# SkyNetV3main.net
KiCad netlist of a schematic drawn in EAGLE
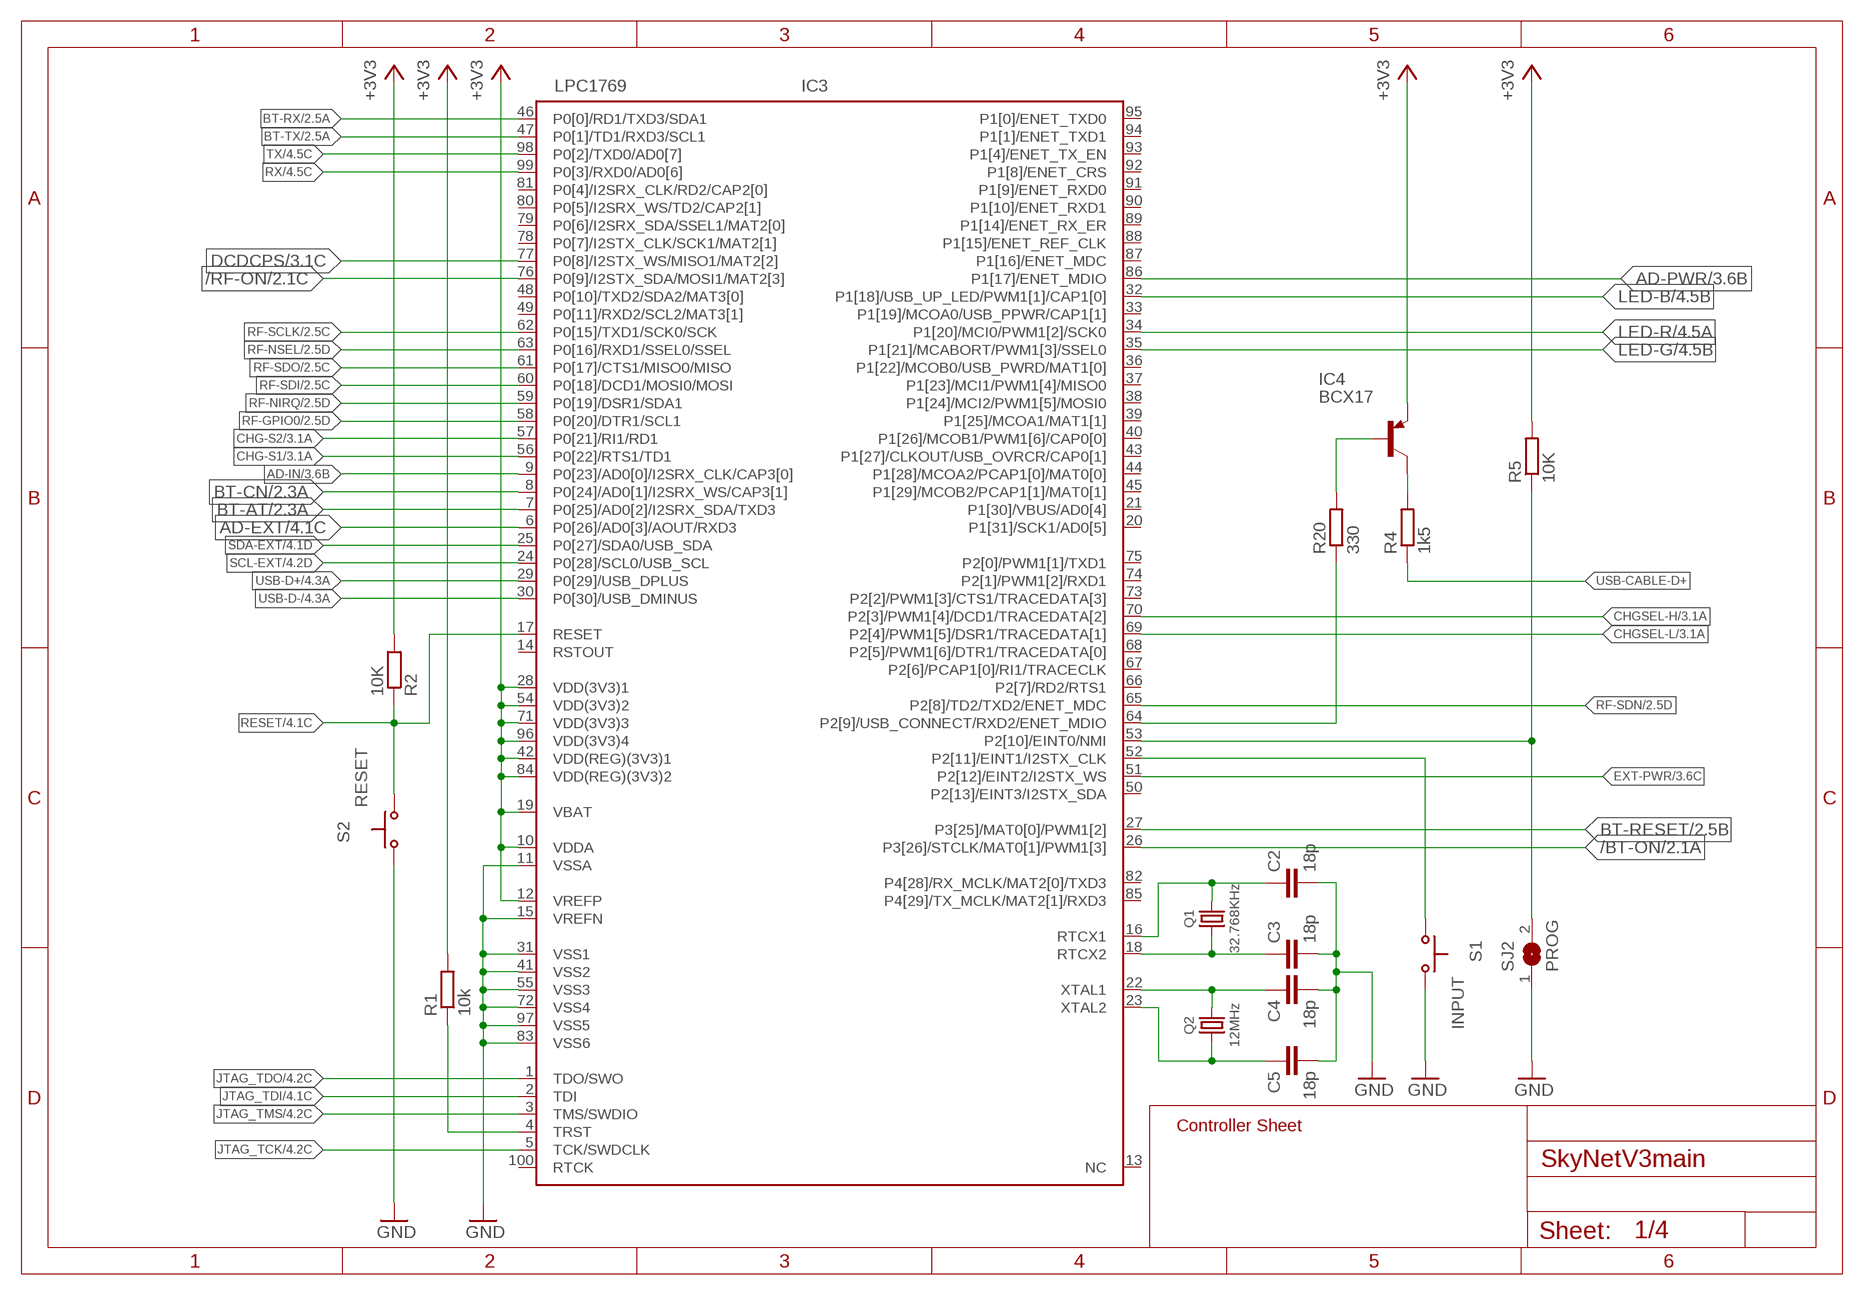
[diagram p0: schematic, sheet 1]
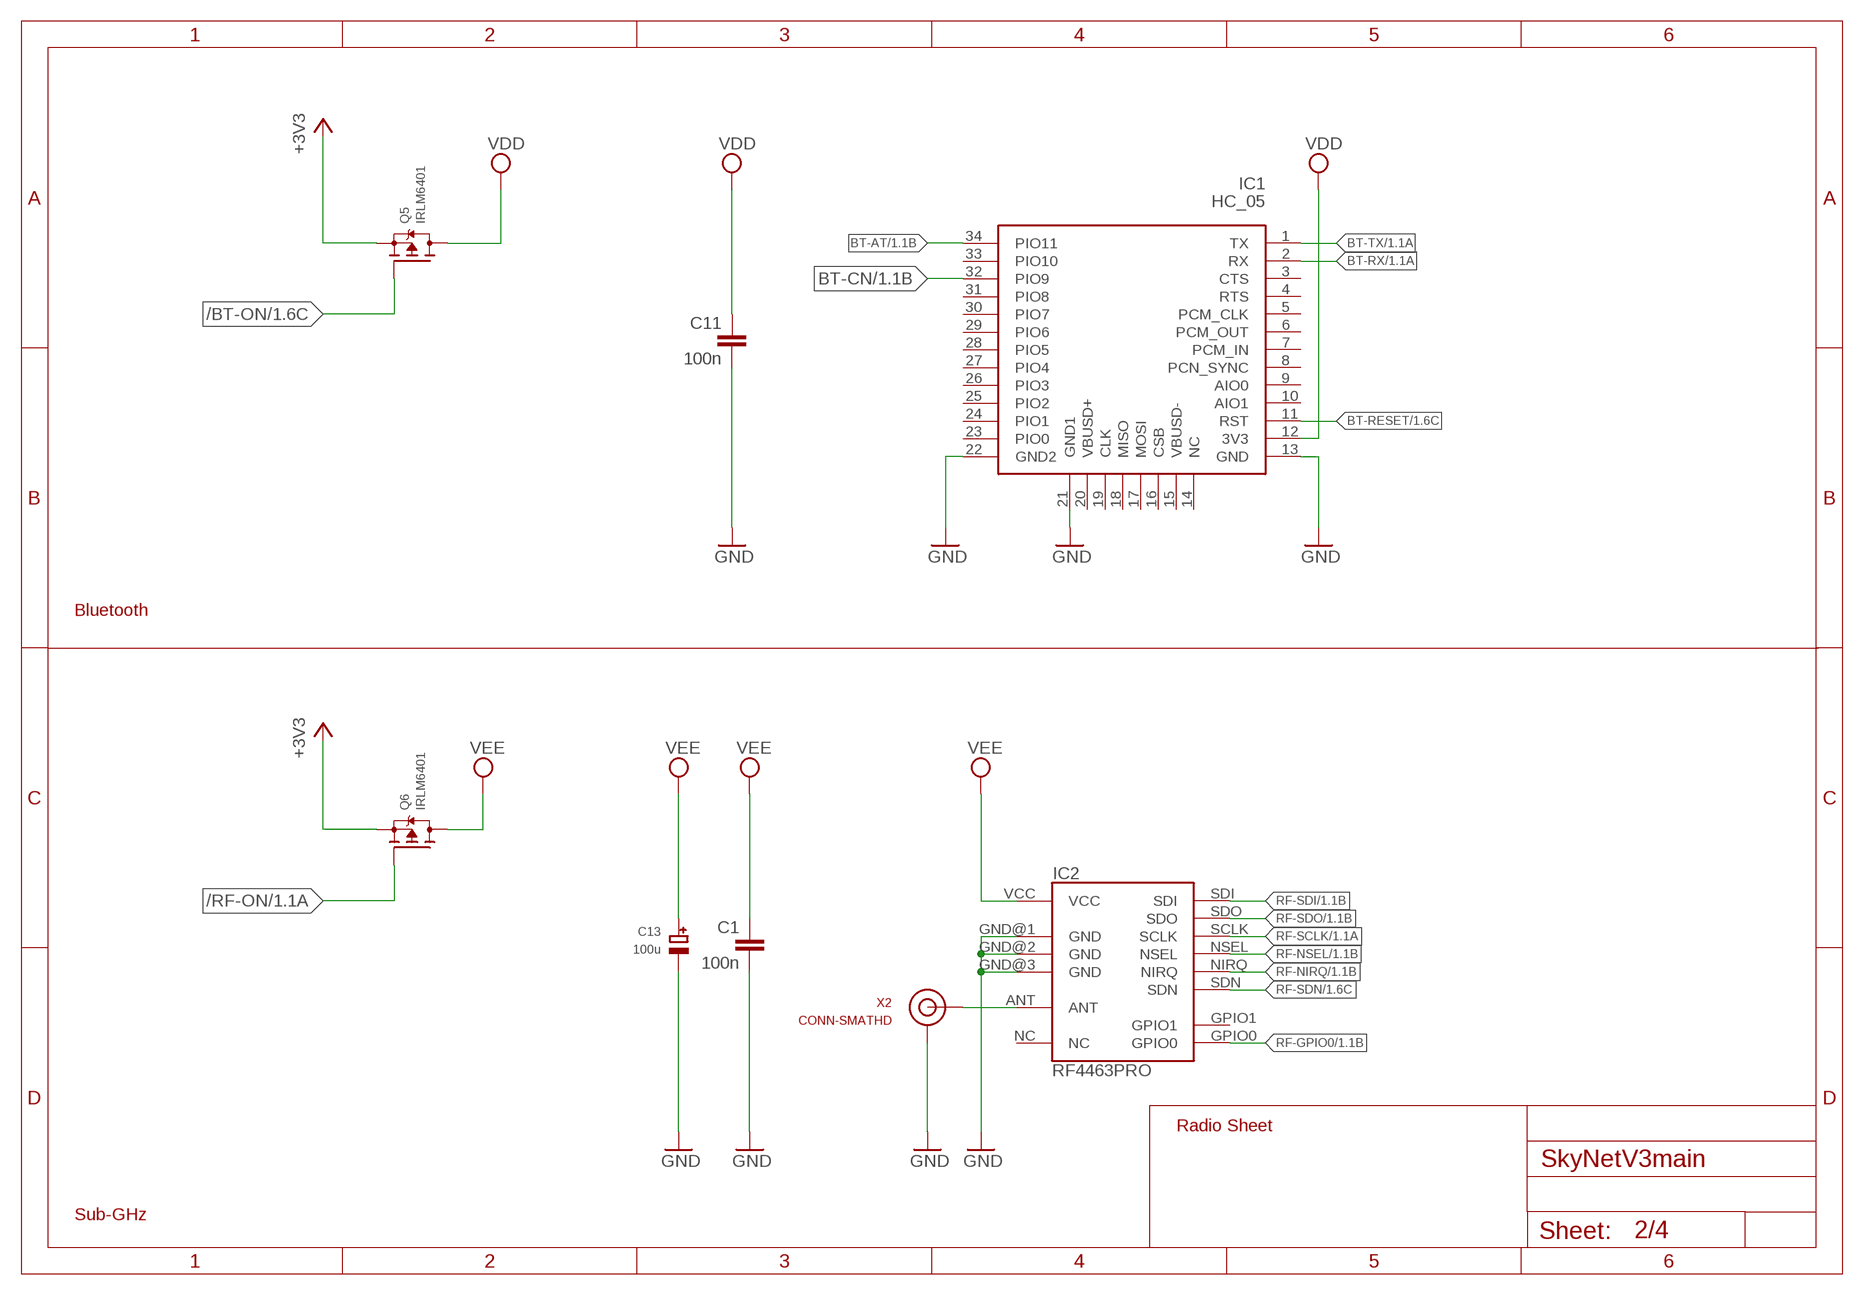
[diagram p1: schematic, sheet 2]
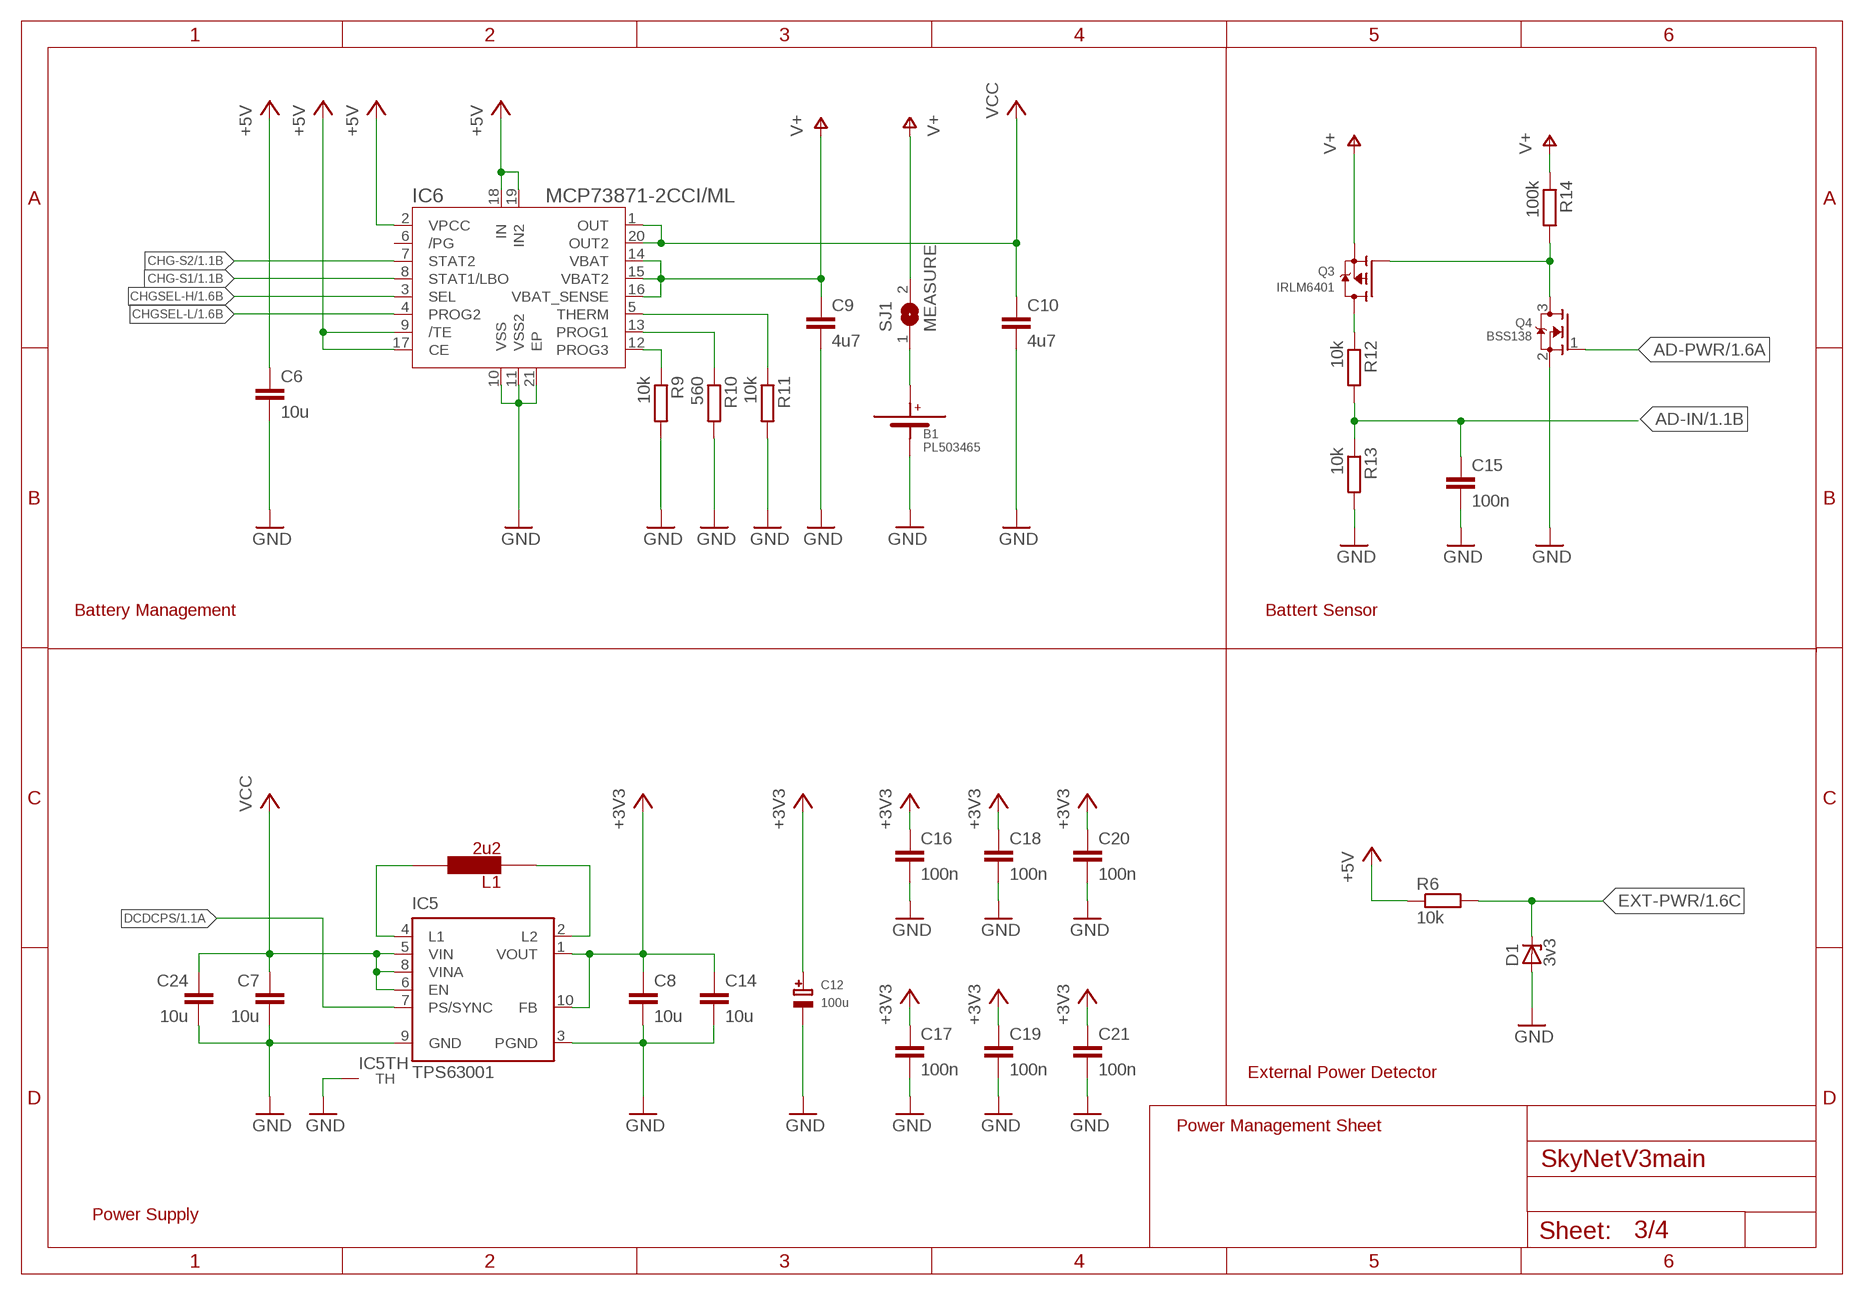
[diagram p2: schematic, sheet 3]
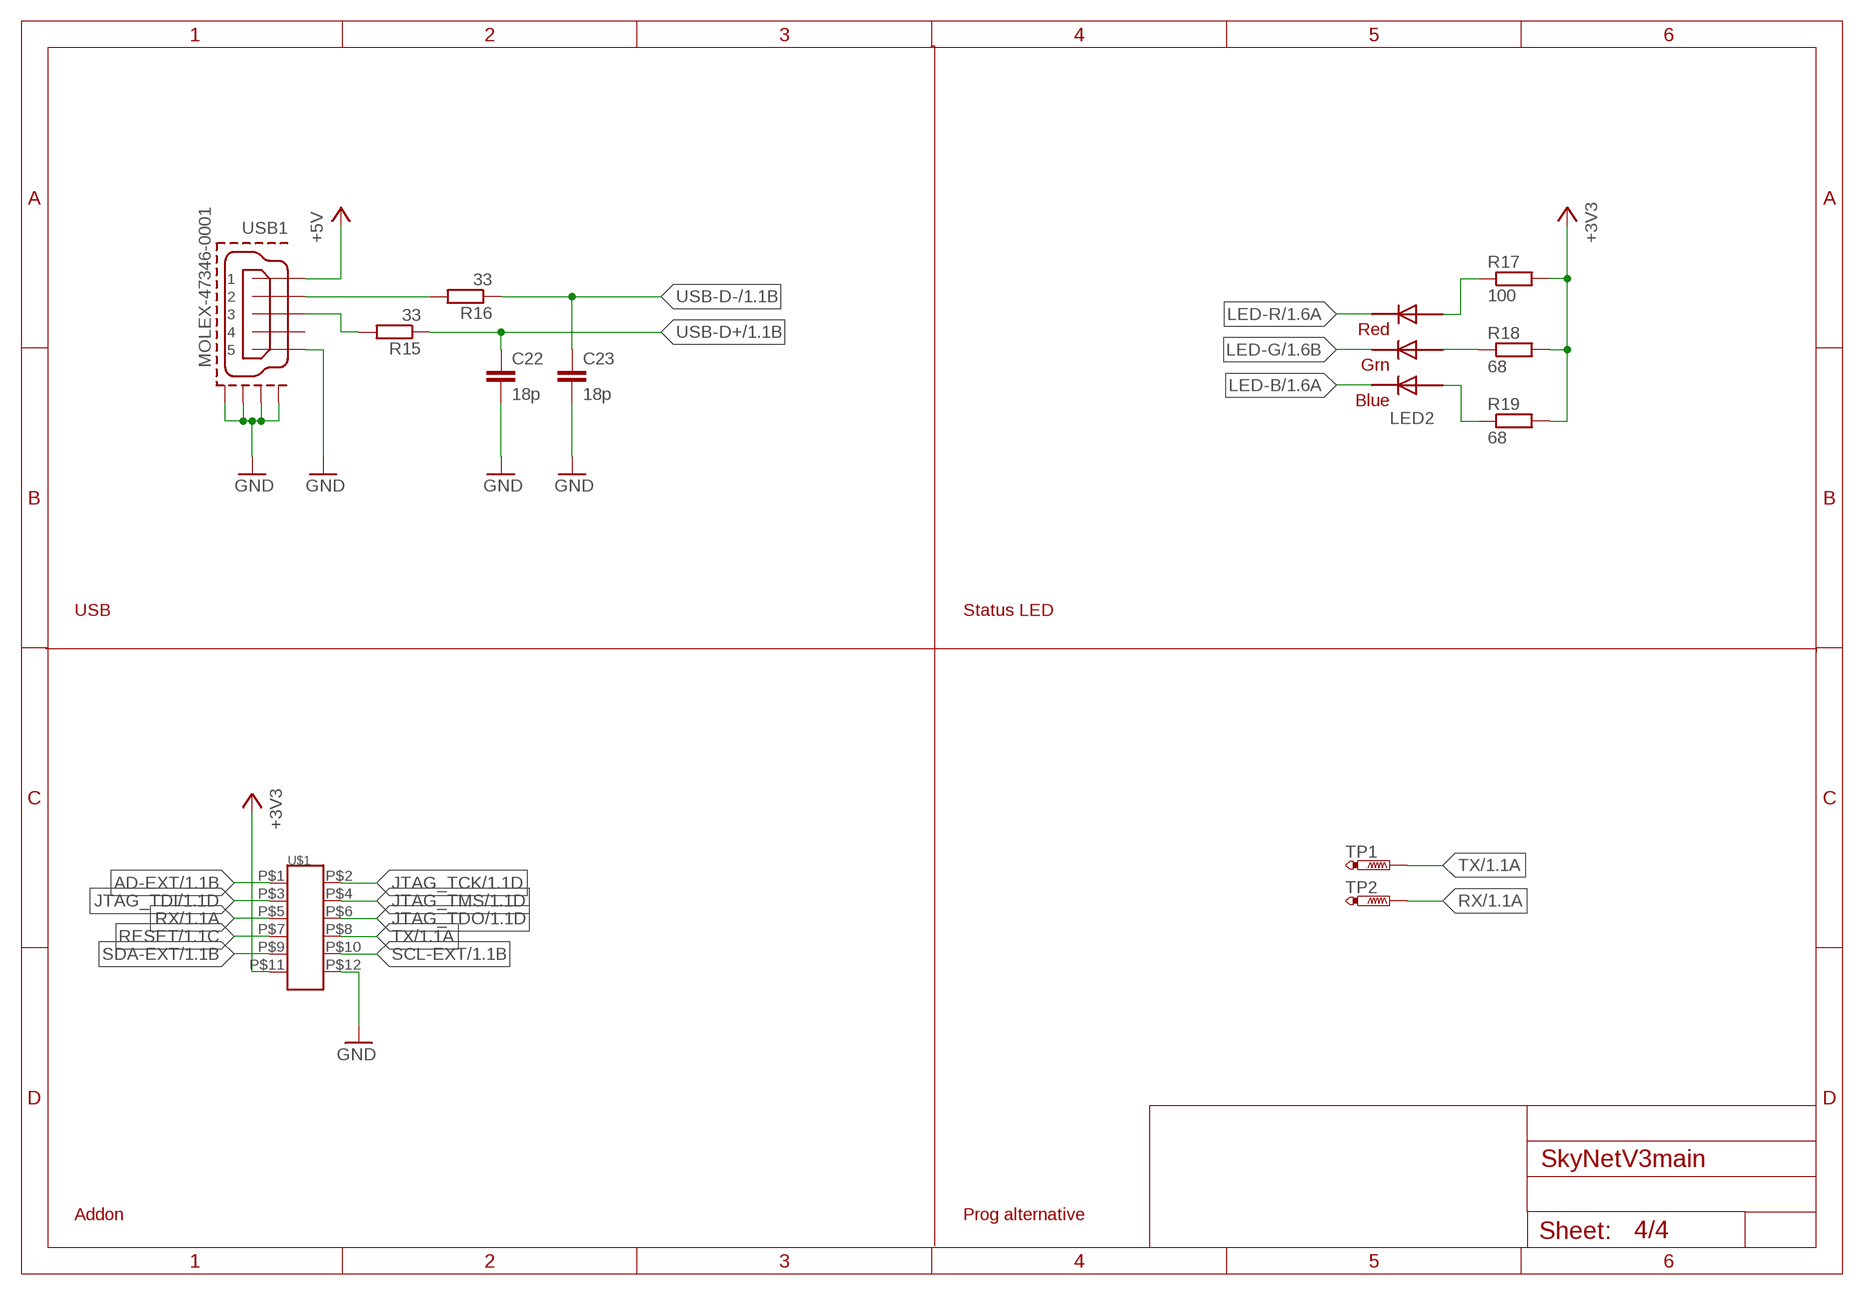
[diagram p3: schematic, sheet 4]

(export (version "E")
  (design (tool "Eeschema 10.0.6"))
  (components
    (comp (ref "B1")
      (value "PL503465")
      (footprint "eagle-import:PL503465")
      (libsource (lib "eagle-import") (part "1S"))
    )
    (comp (ref "C6")
      (value "10u")
      (footprint "eagle-import:C0805")
      (libsource (lib "eagle-import") (part "C-EUC0805"))
    )
    (comp (ref "C7")
      (value "10u")
      (footprint "eagle-import:C1206K")
      (libsource (lib "eagle-import") (part "C-EUC1206K"))
    )
    (comp (ref "C8")
      (value "10u")
      (footprint "eagle-import:C1206K")
      (libsource (lib "eagle-import") (part "C-EUC1206K"))
    )
    (comp (ref "C9")
      (value "4u7")
      (footprint "eagle-import:C1206K")
      (libsource (lib "eagle-import") (part "C-EUC1206K"))
    )
    (comp (ref "C10")
      (value "4u7")
      (footprint "eagle-import:C1206K")
      (libsource (lib "eagle-import") (part "C-EUC1206K"))
    )
    (comp (ref "C12")
      (value "100u")
      (footprint "eagle-import:EIA6032-28_C-W")
      (libsource (lib "eagle-import") (part "CAP_TANTALUMC/6032_WAVE"))
    )
    (comp (ref "C14")
      (value "10u")
      (footprint "eagle-import:C1206K")
      (libsource (lib "eagle-import") (part "C-EUC1206K"))
    )
    (comp (ref "C15")
      (value "100n")
      (footprint "eagle-import:C0603")
      (libsource (lib "eagle-import") (part "C-EUC0603"))
    )
    (comp (ref "C16")
      (value "100n")
      (footprint "eagle-import:C0603")
      (libsource (lib "eagle-import") (part "C-EUC0603"))
    )
    (comp (ref "C17")
      (value "100n")
      (footprint "eagle-import:C0603")
      (libsource (lib "eagle-import") (part "C-EUC0603"))
    )
    (comp (ref "C18")
      (value "100n")
      (footprint "eagle-import:C0603")
      (libsource (lib "eagle-import") (part "C-EUC0603"))
    )
    (comp (ref "C19")
      (value "100n")
      (footprint "eagle-import:C0603")
      (libsource (lib "eagle-import") (part "C-EUC0603"))
    )
    (comp (ref "C20")
      (value "100n")
      (footprint "eagle-import:C0603")
      (libsource (lib "eagle-import") (part "C-EUC0603"))
    )
    (comp (ref "C21")
      (value "100n")
      (footprint "eagle-import:C0603")
      (libsource (lib "eagle-import") (part "C-EUC0603"))
    )
    (comp (ref "C24")
      (value "10u")
      (footprint "eagle-import:C1206K")
      (libsource (lib "eagle-import") (part "C-EUC1206K"))
    )
    (comp (ref "D1")
      (value "3v3")
      (footprint "eagle-import:SOT23")
      (libsource (lib "eagle-import") (part "ZENER-DIODESOT23"))
    )
    (comp (ref "IC5")
      (value "TPS63001")
      (footprint "eagle-import:DRC-S-PVSON-N10")
      (fields (field (name "MPN") "TPS63000DRCTG4"))
      (libsource (lib "eagle-import") (part "TPS6300"))
    )
    (comp (ref "IC6")
      (value "MCP73871-2CCI/ML")
      (footprint "eagle-import:QFN20-4X4")
      (libsource (lib "eagle-import") (part "MCP73871ML-2CCI/"))
    )
    (comp (ref "L1")
      (value "2u2")
      (footprint "eagle-import:LPS4012")
      (libsource (lib "eagle-import") (part "LPS4012"))
    )
    (comp (ref "Q3")
      (value "IRLM6401")
      (footprint "eagle-import:SOT23-WIDE")
      (libsource (lib "eagle-import") (part "MOSFET-PWIDE"))
    )
    (comp (ref "Q4")
      (value "BSS138")
      (footprint "eagle-import:SOT23-WIDE")
      (libsource (lib "eagle-import") (part "MOSFET-NWIDE"))
    )
    (comp (ref "R6")
      (value "10k")
      (footprint "eagle-import:R0603")
      (libsource (lib "eagle-import") (part "R-EU_R0603"))
    )
    (comp (ref "R9")
      (value "10k")
      (footprint "eagle-import:R0603")
      (libsource (lib "eagle-import") (part "R-EU_R0603"))
    )
    (comp (ref "R10")
      (value "560")
      (footprint "eagle-import:R0603")
      (libsource (lib "eagle-import") (part "R-EU_R0603"))
    )
    (comp (ref "R11")
      (value "10k")
      (footprint "eagle-import:R0603")
      (libsource (lib "eagle-import") (part "R-EU_R0603"))
    )
    (comp (ref "R12")
      (value "10k")
      (footprint "eagle-import:R0603")
      (libsource (lib "eagle-import") (part "R-EU_R0603"))
    )
    (comp (ref "R13")
      (value "10k")
      (footprint "eagle-import:R0603")
      (libsource (lib "eagle-import") (part "R-EU_R0603"))
    )
    (comp (ref "R14")
      (value "100k")
      (footprint "eagle-import:R0603")
      (libsource (lib "eagle-import") (part "R-EU_R0603"))
    )
    (comp (ref "SJ1")
      (value "MEASURE")
      (footprint "eagle-import:SJ")
      (libsource (lib "eagle-import") (part "SJ"))
    )
    (comp (ref "C2")
      (value "18p")
      (footprint "eagle-import:C0603")
      (libsource (lib "eagle-import") (part "C-EUC0603"))
    )
    (comp (ref "C3")
      (value "18p")
      (footprint "eagle-import:C0603")
      (libsource (lib "eagle-import") (part "C-EUC0603"))
    )
    (comp (ref "C4")
      (value "18p")
      (footprint "eagle-import:C0603")
      (libsource (lib "eagle-import") (part "C-EUC0603"))
    )
    (comp (ref "C5")
      (value "18p")
      (footprint "eagle-import:C0603")
      (libsource (lib "eagle-import") (part "C-EUC0603"))
    )
    (comp (ref "IC3")
      (value "LPC1769")
      (footprint "eagle-import:LQFP100-14X14")
      (libsource (lib "eagle-import") (part "LPC1768"))
    )
    (comp (ref "IC4")
      (value "BCX17")
      (footprint "eagle-import:SOT23")
      (libsource (lib "eagle-import") (part "BCX17"))
    )
    (comp (ref "Q1")
      (value "32.768KHz")
      (footprint "eagle-import:XTAL_49_18")
      (libsource (lib "eagle-import") (part "XTAL2-PAD"))
    )
    (comp (ref "Q2")
      (value "12MHz")
      (footprint "eagle-import:XTAL_50_32")
      (libsource (lib "eagle-import") (part "XTAL4-PAD"))
    )
    (comp (ref "R1")
      (value "10k")
      (footprint "eagle-import:R0603")
      (libsource (lib "eagle-import") (part "R-EU_R0603"))
    )
    (comp (ref "R2")
      (value "10K")
      (footprint "eagle-import:R0603")
      (libsource (lib "eagle-import") (part "R-EU_R0603"))
    )
    (comp (ref "R4")
      (value "1k5")
      (footprint "eagle-import:R0603")
      (libsource (lib "eagle-import") (part "R-EU_R0603"))
    )
    (comp (ref "R5")
      (value "10K")
      (footprint "eagle-import:R0603")
      (libsource (lib "eagle-import") (part "R-EU_R0603"))
    )
    (comp (ref "R20")
      (value "330")
      (footprint "eagle-import:R0603")
      (libsource (lib "eagle-import") (part "R-EU_R0603"))
    )
    (comp (ref "S1")
      (value "INPUT")
      (footprint "eagle-import:PTS645-SMD")
      (libsource (lib "eagle-import") (part "PTS645S???SMTR"))
    )
    (comp (ref "S2")
      (value "RESET")
      (footprint "eagle-import:PTS645-SMD")
      (libsource (lib "eagle-import") (part "PTS645S???SMTR"))
    )
    (comp (ref "SJ2")
      (value "PROG")
      (footprint "eagle-import:SJ")
      (libsource (lib "eagle-import") (part "SJ"))
    )
    (comp (ref "C1")
      (value "100n")
      (footprint "eagle-import:C1206K")
      (libsource (lib "eagle-import") (part "C-EUC1206K"))
    )
    (comp (ref "C11")
      (value "100n")
      (footprint "eagle-import:C1206K")
      (libsource (lib "eagle-import") (part "C-EUC1206K"))
    )
    (comp (ref "C13")
      (value "100u")
      (footprint "eagle-import:EIA6032-28_C-W")
      (libsource (lib "eagle-import") (part "CAP_TANTALUMC/6032_WAVE"))
    )
    (comp (ref "IC1")
      (value "HC_05")
      (footprint "eagle-import:BLUETOOTH_SMD")
      (libsource (lib "eagle-import") (part "HC_05"))
    )
    (comp (ref "IC2")
      (value "RF4463PRO")
      (footprint "eagle-import:STD_BOARD")
      (libsource (lib "eagle-import") (part "RF4463PRO"))
    )
    (comp (ref "Q5")
      (value "IRLM6401")
      (footprint "eagle-import:SOT23-WIDE")
      (libsource (lib "eagle-import") (part "MOSFET-PWIDE"))
    )
    (comp (ref "Q6")
      (value "IRLM6401")
      (footprint "eagle-import:SOT23-WIDE")
      (libsource (lib "eagle-import") (part "MOSFET-PWIDE"))
    )
    (comp (ref "X2")
      (value "CONN-SMATHD")
      (footprint "eagle-import:SMA-THD")
      (libsource (lib "eagle-import") (part "CONN-SMATHD"))
    )
    (comp (ref "C22")
      (value "18p")
      (footprint "eagle-import:C0603")
      (libsource (lib "eagle-import") (part "C-EUC0603"))
    )
    (comp (ref "C23")
      (value "18p")
      (footprint "eagle-import:C0603")
      (libsource (lib "eagle-import") (part "C-EUC0603"))
    )
    (comp (ref "LED2")
      (value "RGBLED5050")
      (footprint "eagle-import:RGBLED5050")
      (libsource (lib "eagle-import") (part "RGBLED5050"))
    )
    (comp (ref "R15")
      (value "33")
      (footprint "eagle-import:R0603")
      (libsource (lib "eagle-import") (part "R-EU_R0603"))
    )
    (comp (ref "R16")
      (value "33")
      (footprint "eagle-import:R0603")
      (libsource (lib "eagle-import") (part "R-EU_R0603"))
    )
    (comp (ref "R17")
      (value "100")
      (footprint "eagle-import:R0603")
      (libsource (lib "eagle-import") (part "R-EU_R0603"))
    )
    (comp (ref "R18")
      (value "68")
      (footprint "eagle-import:R0603")
      (libsource (lib "eagle-import") (part "R-EU_R0603"))
    )
    (comp (ref "R19")
      (value "68")
      (footprint "eagle-import:R0603")
      (libsource (lib "eagle-import") (part "R-EU_R0603"))
    )
    (comp (ref "TP1")
      (value "PTR1B1,27")
      (footprint "eagle-import:B1,27")
      (libsource (lib "eagle-import") (part "PTR1B1,27"))
    )
    (comp (ref "TP2")
      (value "PTR1B1,27")
      (footprint "eagle-import:B1,27")
      (libsource (lib "eagle-import") (part "PTR1B1,27"))
    )
    (comp (ref "U$1")
      (value "2X6SMD2.0")
      (footprint "eagle-import:2X6SMD2.00")
      (libsource (lib "eagle-import") (part "2X6SMD2.0"))
    )
    (comp (ref "USB1")
      (value "MOLEX-47346-0001")
      (footprint "eagle-import:MOLEX-47364-0001")
      (libsource (lib "eagle-import") (part "MOLEX-47346-0001"))
    )
  )
  (nets
    (net (code "1") (name "+3V3") (class "Default")
      (node (ref "C12") (pin "+") (pinfunction "+_+") (pintype "passive"))
      (node (ref "C14") (pin "1") (pinfunction "1_1") (pintype "passive"))
      (node (ref "C16") (pin "1") (pinfunction "1_1") (pintype "passive"))
      (node (ref "C17") (pin "1") (pinfunction "1_1") (pintype "passive"))
      (node (ref "C18") (pin "1") (pinfunction "1_1") (pintype "passive"))
      (node (ref "C19") (pin "1") (pinfunction "1_1") (pintype "passive"))
      (node (ref "C20") (pin "1") (pinfunction "1_1") (pintype "passive"))
      (node (ref "C21") (pin "1") (pinfunction "1_1") (pintype "passive"))
      (node (ref "C8") (pin "1") (pinfunction "1_1") (pintype "passive"))
      (node (ref "IC3") (pin "10") (pinfunction "VDDA_10") (pintype "bidirectional"))
      (node (ref "IC3") (pin "12") (pinfunction "VREFP_12") (pintype "bidirectional"))
      (node (ref "IC3") (pin "19") (pinfunction "VBAT_19") (pintype "bidirectional"))
      (node (ref "IC3") (pin "28") (pinfunction "VDD(3V3)1_28") (pintype "bidirectional"))
      (node (ref "IC3") (pin "42") (pinfunction "VDD(REG)(3V3)1_42") (pintype "bidirectional"))
      (node (ref "IC3") (pin "54") (pinfunction "VDD(3V3)2_54") (pintype "bidirectional"))
      (node (ref "IC3") (pin "71") (pinfunction "VDD(3V3)3_71") (pintype "bidirectional"))
      (node (ref "IC3") (pin "84") (pinfunction "VDD(REG)(3V3)2_84") (pintype "bidirectional"))
      (node (ref "IC3") (pin "96") (pinfunction "VDD(3V3)4_96") (pintype "bidirectional"))
      (node (ref "IC4") (pin "2") (pinfunction "E_2") (pintype "passive"))
      (node (ref "IC5") (pin "1") (pinfunction "VOUT_1") (pintype "output"))
      (node (ref "IC5") (pin "10") (pinfunction "FB_10") (pintype "input"))
      (node (ref "Q5") (pin "2") (pinfunction "S_2") (pintype "passive"))
      (node (ref "Q6") (pin "2") (pinfunction "S_2") (pintype "passive"))
      (node (ref "R1") (pin "2") (pinfunction "2_2") (pintype "passive"))
      (node (ref "R17") (pin "2") (pinfunction "2_2") (pintype "passive"))
      (node (ref "R18") (pin "2") (pinfunction "2_2") (pintype "passive"))
      (node (ref "R19") (pin "2") (pinfunction "2_2") (pintype "passive"))
      (node (ref "R2") (pin "2") (pinfunction "2_2") (pintype "passive"))
      (node (ref "R5") (pin "2") (pinfunction "2_2") (pintype "passive"))
      (node (ref "U$1") (pin "P$11") (pinfunction "P$11_P$11") (pintype "bidirectional"))
    )
    (net (code "2") (name "+5V") (class "Default")
      (node (ref "C6") (pin "1") (pinfunction "1_1") (pintype "passive"))
      (node (ref "IC6") (pin "17") (pinfunction "CE_17") (pintype "input"))
      (node (ref "IC6") (pin "18") (pinfunction "IN_18") (pintype "power_in"))
      (node (ref "IC6") (pin "19") (pinfunction "IN2_19") (pintype "power_in"))
      (node (ref "IC6") (pin "2") (pinfunction "VPCC_2") (pintype "input"))
      (node (ref "IC6") (pin "9") (pinfunction "/TE_9") (pintype "input"))
      (node (ref "R6") (pin "1") (pinfunction "1_1") (pintype "passive"))
      (node (ref "USB1") (pin "1") (pinfunction "1_1") (pintype "input"))
    )
    (net (code "3") (name "AD-EXT") (class "Default")
      (node (ref "IC3") (pin "6") (pinfunction "P0[26]/AD0[3]/AOUT/RXD3_6") (pintype "bidirectional"))
      (node (ref "U$1") (pin "P$1") (pinfunction "P$1_P$1") (pintype "bidirectional"))
    )
    (net (code "4") (name "AD-IN") (class "Default")
      (node (ref "C15") (pin "1") (pinfunction "1_1") (pintype "passive"))
      (node (ref "IC3") (pin "9") (pinfunction "P0[23]/AD0[0]/I2SRX_CLK/CAP3[0]_9") (pintype "bidirectional"))
      (node (ref "R12") (pin "2") (pinfunction "2_2") (pintype "passive"))
      (node (ref "R13") (pin "1") (pinfunction "1_1") (pintype "passive"))
    )
    (net (code "5") (name "AD-PWR") (class "Default")
      (node (ref "IC3") (pin "86") (pinfunction "P1[17]/ENET_MDIO_86") (pintype "bidirectional"))
      (node (ref "Q4") (pin "1") (pinfunction "G_1") (pintype "bidirectional"))
    )
    (net (code "6") (name "BT-AT") (class "Default")
      (node (ref "IC1") (pin "34") (pinfunction "PIO11_34") (pintype "bidirectional"))
      (node (ref "IC3") (pin "7") (pinfunction "P0[25]/AD0[2]/I2SRX_SDA/TXD3_7") (pintype "bidirectional"))
    )
    (net (code "7") (name "BT-CN") (class "Default")
      (node (ref "IC1") (pin "32") (pinfunction "PIO9_32") (pintype "bidirectional"))
      (node (ref "IC3") (pin "8") (pinfunction "P0[24]/AD0[1]/I2SRX_WS/CAP3[1]_8") (pintype "bidirectional"))
    )
    (net (code "8") (name "BT-RESET") (class "Default")
      (node (ref "IC1") (pin "11") (pinfunction "RST_11") (pintype "bidirectional"))
      (node (ref "IC3") (pin "27") (pinfunction "P3[25]/MAT0[0]/PWM1[2]_27") (pintype "bidirectional"))
    )
    (net (code "9") (name "BT-RX") (class "Default")
      (node (ref "IC1") (pin "2") (pinfunction "RX_2") (pintype "bidirectional"))
      (node (ref "IC3") (pin "46") (pinfunction "P0[0]/RD1/TXD3/SDA1_46") (pintype "bidirectional"))
    )
    (net (code "10") (name "BT-TX") (class "Default")
      (node (ref "IC1") (pin "1") (pinfunction "TX_1") (pintype "bidirectional"))
      (node (ref "IC3") (pin "47") (pinfunction "P0[1]/TD1/RXD3/SCL1_47") (pintype "bidirectional"))
    )
    (net (code "11") (name "CHG-S1") (class "Default")
      (node (ref "IC3") (pin "56") (pinfunction "P0[22]/RTS1/TD1_56") (pintype "bidirectional"))
      (node (ref "IC6") (pin "8") (pinfunction "STAT1/LBO_8") (pintype "open_collector"))
    )
    (net (code "12") (name "CHG-S2") (class "Default")
      (node (ref "IC3") (pin "57") (pinfunction "P0[21]/RI1/RD1_57") (pintype "bidirectional"))
      (node (ref "IC6") (pin "7") (pinfunction "STAT2_7") (pintype "open_collector"))
    )
    (net (code "13") (name "CHGSEL-H") (class "Default")
      (node (ref "IC3") (pin "70") (pinfunction "P2[3]/PWM1[4]/DCD1/TRACEDATA[2]_70") (pintype "bidirectional"))
      (node (ref "IC6") (pin "3") (pinfunction "SEL_3") (pintype "input"))
    )
    (net (code "14") (name "CHGSEL-L") (class "Default")
      (node (ref "IC3") (pin "69") (pinfunction "P2[4]/PWM1[5]/DSR1/TRACEDATA[1]_69") (pintype "bidirectional"))
      (node (ref "IC6") (pin "4") (pinfunction "PROG2_4") (pintype "input"))
    )
    (net (code "15") (name "DCDCPS") (class "Default")
      (node (ref "IC3") (pin "77") (pinfunction "P0[8]/I2STX_WS/MISO1/MAT2[2]_77") (pintype "bidirectional"))
      (node (ref "IC5") (pin "7") (pinfunction "PS/SYNC_7") (pintype "input"))
    )
    (net (code "16") (name "EXT-PWR") (class "Default")
      (node (ref "D1") (pin "3") (pinfunction "C_3") (pintype "passive"))
      (node (ref "IC3") (pin "51") (pinfunction "P2[12]/EINT2/I2STX_WS_51") (pintype "bidirectional"))
      (node (ref "R6") (pin "2") (pinfunction "2_2") (pintype "passive"))
    )
    (net (code "17") (name "GND") (class "Default")
      (node (ref "B1") (pin "P-") (pinfunction "P-_P-") (pintype "bidirectional"))
      (node (ref "C1") (pin "2") (pinfunction "2_2") (pintype "passive"))
      (node (ref "C10") (pin "2") (pinfunction "2_2") (pintype "passive"))
      (node (ref "C11") (pin "2") (pinfunction "2_2") (pintype "passive"))
      (node (ref "C12") (pin "-") (pinfunction "-_-") (pintype "passive"))
      (node (ref "C13") (pin "-") (pinfunction "-_-") (pintype "passive"))
      (node (ref "C14") (pin "2") (pinfunction "2_2") (pintype "passive"))
      (node (ref "C15") (pin "2") (pinfunction "2_2") (pintype "passive"))
      (node (ref "C16") (pin "2") (pinfunction "2_2") (pintype "passive"))
      (node (ref "C17") (pin "2") (pinfunction "2_2") (pintype "passive"))
      (node (ref "C18") (pin "2") (pinfunction "2_2") (pintype "passive"))
      (node (ref "C19") (pin "2") (pinfunction "2_2") (pintype "passive"))
      (node (ref "C2") (pin "2") (pinfunction "2_2") (pintype "passive"))
      (node (ref "C20") (pin "2") (pinfunction "2_2") (pintype "passive"))
      (node (ref "C21") (pin "2") (pinfunction "2_2") (pintype "passive"))
      (node (ref "C22") (pin "2") (pinfunction "2_2") (pintype "passive"))
      (node (ref "C23") (pin "2") (pinfunction "2_2") (pintype "passive"))
      (node (ref "C24") (pin "2") (pinfunction "2_2") (pintype "passive"))
      (node (ref "C3") (pin "2") (pinfunction "2_2") (pintype "passive"))
      (node (ref "C4") (pin "2") (pinfunction "2_2") (pintype "passive"))
      (node (ref "C5") (pin "2") (pinfunction "2_2") (pintype "passive"))
      (node (ref "C6") (pin "2") (pinfunction "2_2") (pintype "passive"))
      (node (ref "C7") (pin "2") (pinfunction "2_2") (pintype "passive"))
      (node (ref "C8") (pin "2") (pinfunction "2_2") (pintype "passive"))
      (node (ref "C9") (pin "2") (pinfunction "2_2") (pintype "passive"))
      (node (ref "D1") (pin "1") (pinfunction "A_1") (pintype "passive"))
      (node (ref "IC1") (pin "13") (pinfunction "GND_13") (pintype "bidirectional"))
      (node (ref "IC1") (pin "21") (pinfunction "GND1_21") (pintype "bidirectional"))
      (node (ref "IC1") (pin "22") (pinfunction "GND2_22") (pintype "bidirectional"))
      (node (ref "IC2") (pin "GND@1") (pinfunction "GND_GND@1") (pintype "power_in"))
      (node (ref "IC2") (pin "GND@2") (pinfunction "GND_GND@2") (pintype "power_in"))
      (node (ref "IC2") (pin "GND@3") (pinfunction "GND_GND@3") (pintype "power_in"))
      (node (ref "IC3") (pin "11") (pinfunction "VSSA_11") (pintype "bidirectional"))
      (node (ref "IC3") (pin "15") (pinfunction "VREFN_15") (pintype "bidirectional"))
      (node (ref "IC3") (pin "31") (pinfunction "VSS1_31") (pintype "bidirectional"))
      (node (ref "IC3") (pin "41") (pinfunction "VSS2_41") (pintype "bidirectional"))
      (node (ref "IC3") (pin "55") (pinfunction "VSS3_55") (pintype "bidirectional"))
      (node (ref "IC3") (pin "72") (pinfunction "VSS4_72") (pintype "bidirectional"))
      (node (ref "IC3") (pin "83") (pinfunction "VSS6_83") (pintype "bidirectional"))
      (node (ref "IC3") (pin "97") (pinfunction "VSS5_97") (pintype "bidirectional"))
      (node (ref "IC5") (pin "3") (pinfunction "PGND_3") (pintype "power_in"))
      (node (ref "IC5") (pin "9") (pinfunction "GND_9") (pintype "power_in"))
      (node (ref "IC5") (pin "TH") (pinfunction "TH_TH") (pintype "passive"))
      (node (ref "IC6") (pin "10") (pinfunction "VSS_10") (pintype "power_in"))
      (node (ref "IC6") (pin "11") (pinfunction "VSS2_11") (pintype "power_in"))
      (node (ref "IC6") (pin "21") (pinfunction "EP_21") (pintype "power_in"))
      (node (ref "Q4") (pin "2") (pinfunction "S_2") (pintype "bidirectional"))
      (node (ref "R10") (pin "2") (pinfunction "2_2") (pintype "passive"))
      (node (ref "R11") (pin "2") (pinfunction "2_2") (pintype "passive"))
      (node (ref "R13") (pin "2") (pinfunction "2_2") (pintype "passive"))
      (node (ref "R9") (pin "2") (pinfunction "2_2") (pintype "passive"))
      (node (ref "S1") (pin "3") (pinfunction "S_3") (pintype "passive"))
      (node (ref "S1") (pin "4") (pinfunction "S_4") (pintype "passive"))
      (node (ref "S2") (pin "1") (pinfunction "P_1") (pintype "passive"))
      (node (ref "S2") (pin "2") (pinfunction "P_2") (pintype "passive"))
      (node (ref "SJ2") (pin "1") (pinfunction "1_1") (pintype "passive"))
      (node (ref "U$1") (pin "P$12") (pinfunction "P$12_P$12") (pintype "bidirectional"))
      (node (ref "USB1") (pin "5") (pinfunction "5_5") (pintype "input"))
      (node (ref "USB1") (pin "GND1") (pinfunction "GND1_GND1") (pintype "bidirectional"))
      (node (ref "USB1") (pin "GND2") (pinfunction "GND2_GND2") (pintype "bidirectional"))
      (node (ref "USB1") (pin "GND3") (pinfunction "GND3_GND3") (pintype "bidirectional"))
      (node (ref "USB1") (pin "GND4") (pinfunction "GND4_GND4") (pintype "bidirectional"))
      (node (ref "X2") (pin "GND@0") (pinfunction "GND_GND@0") (pintype "bidirectional"))
      (node (ref "X2") (pin "GND@1") (pinfunction "GND_GND@1") (pintype "bidirectional"))
      (node (ref "X2") (pin "GND@2") (pinfunction "GND_GND@2") (pintype "bidirectional"))
      (node (ref "X2") (pin "GND@3") (pinfunction "GND_GND@3") (pintype "bidirectional"))
    )
    (net (code "18") (name "JTAG_TCK") (class "Default")
      (node (ref "IC3") (pin "5") (pinfunction "TCK/SWDCLK_5") (pintype "bidirectional"))
      (node (ref "U$1") (pin "P$2") (pinfunction "P$2_P$2") (pintype "bidirectional"))
    )
    (net (code "19") (name "JTAG_TDI") (class "Default")
      (node (ref "IC3") (pin "2") (pinfunction "TDI_2") (pintype "bidirectional"))
      (node (ref "U$1") (pin "P$3") (pinfunction "P$3_P$3") (pintype "bidirectional"))
    )
    (net (code "20") (name "JTAG_TDO") (class "Default")
      (node (ref "IC3") (pin "1") (pinfunction "TDO/SWO_1") (pintype "bidirectional"))
      (node (ref "U$1") (pin "P$6") (pinfunction "P$6_P$6") (pintype "bidirectional"))
    )
    (net (code "21") (name "JTAG_TMS") (class "Default")
      (node (ref "IC3") (pin "3") (pinfunction "TMS/SWDIO_3") (pintype "bidirectional"))
      (node (ref "U$1") (pin "P$4") (pinfunction "P$4_P$4") (pintype "bidirectional"))
    )
    (net (code "22") (name "LED-B") (class "Default")
      (node (ref "IC3") (pin "32") (pinfunction "P1[18]/USB_UP_LED/PWM1[1]/CAP1[0]_32") (pintype "bidirectional"))
      (node (ref "LED2") (pin "4") (pinfunction "BLUE_C_4") (pintype "bidirectional"))
    )
    (net (code "23") (name "LED-G") (class "Default")
      (node (ref "IC3") (pin "35") (pinfunction "P1[21]/MCABORT/PWM1[3]/SSEL0_35") (pintype "bidirectional"))
      (node (ref "LED2") (pin "6") (pinfunction "GREEN_C_6") (pintype "bidirectional"))
    )
    (net (code "24") (name "LED-R") (class "Default")
      (node (ref "IC3") (pin "34") (pinfunction "P1[20]/MCI0/PWM1[2]/SCK0_34") (pintype "bidirectional"))
      (node (ref "LED2") (pin "5") (pinfunction "RED_C_5") (pintype "bidirectional"))
    )
    (net (code "25") (name "Net-(B1-PadP+)") (class "Default")
      (node (ref "B1") (pin "P+") (pinfunction "P+_P+") (pintype "bidirectional"))
      (node (ref "SJ1") (pin "1") (pinfunction "1_1") (pintype "passive"))
    )
    (net (code "26") (name "Net-(IC3-P2[9]{slash}USB_CONNECT{slash}RXD2{slash}ENET_MDIO)") (class "Default")
      (node (ref "IC3") (pin "64") (pinfunction "P2[9]/USB_CONNECT/RXD2/ENET_MDIO_64") (pintype "bidirectional"))
      (node (ref "R20") (pin "1") (pinfunction "1_1") (pintype "passive"))
    )
    (net (code "27") (name "Net-(IC3-P2[10]{slash}EINT0{slash}NMI)") (class "Default")
      (node (ref "IC3") (pin "53") (pinfunction "P2[10]/EINT0/NMI_53") (pintype "bidirectional"))
      (node (ref "R5") (pin "1") (pinfunction "1_1") (pintype "passive"))
      (node (ref "SJ2") (pin "2") (pinfunction "2_2") (pintype "passive"))
    )
    (net (code "28") (name "Net-(IC3-P2[11]{slash}EINT1{slash}I2STX_CLK)") (class "Default")
      (node (ref "IC3") (pin "52") (pinfunction "P2[11]/EINT1/I2STX_CLK_52") (pintype "bidirectional"))
      (node (ref "S1") (pin "1") (pinfunction "P_1") (pintype "passive"))
      (node (ref "S1") (pin "2") (pinfunction "P_2") (pintype "passive"))
    )
    (net (code "29") (name "Net-(IC3-RTCX1)") (class "Default")
      (node (ref "C2") (pin "1") (pinfunction "1_1") (pintype "passive"))
      (node (ref "IC3") (pin "16") (pinfunction "RTCX1_16") (pintype "bidirectional"))
      (node (ref "Q1") (pin "2") (pinfunction "2_2") (pintype "passive"))
    )
    (net (code "30") (name "Net-(IC3-RTCX2)") (class "Default")
      (node (ref "C3") (pin "1") (pinfunction "1_1") (pintype "passive"))
      (node (ref "IC3") (pin "18") (pinfunction "RTCX2_18") (pintype "bidirectional"))
      (node (ref "Q1") (pin "1") (pinfunction "1_1") (pintype "passive"))
    )
    (net (code "31") (name "Net-(IC3-TRST)") (class "Default")
      (node (ref "IC3") (pin "4") (pinfunction "TRST_4") (pintype "bidirectional"))
      (node (ref "R1") (pin "1") (pinfunction "1_1") (pintype "passive"))
    )
    (net (code "32") (name "Net-(IC3-XTAL1)") (class "Default")
      (node (ref "C4") (pin "1") (pinfunction "1_1") (pintype "passive"))
      (node (ref "IC3") (pin "22") (pinfunction "XTAL1_22") (pintype "bidirectional"))
      (node (ref "Q2") (pin "3") (pinfunction "2_3") (pintype "passive"))
    )
    (net (code "33") (name "Net-(IC3-XTAL2)") (class "Default")
      (node (ref "C5") (pin "1") (pinfunction "1_1") (pintype "passive"))
      (node (ref "IC3") (pin "23") (pinfunction "XTAL2_23") (pintype "bidirectional"))
      (node (ref "Q2") (pin "1") (pinfunction "1_1") (pintype "passive"))
    )
    (net (code "34") (name "Net-(IC4-B)") (class "Default")
      (node (ref "IC4") (pin "1") (pinfunction "B_1") (pintype "passive"))
      (node (ref "R20") (pin "2") (pinfunction "2_2") (pintype "passive"))
    )
    (net (code "35") (name "Net-(IC4-C)") (class "Default")
      (node (ref "IC4") (pin "3") (pinfunction "C_3") (pintype "passive"))
      (node (ref "R4") (pin "2") (pinfunction "2_2") (pintype "passive"))
    )
    (net (code "36") (name "Net-(IC5A-L1)") (class "Default")
      (node (ref "IC5") (pin "4") (pinfunction "L1_4") (pintype "passive"))
      (node (ref "L1") (pin "1") (pinfunction "P1_1") (pintype "bidirectional"))
    )
    (net (code "37") (name "Net-(IC5A-L2)") (class "Default")
      (node (ref "IC5") (pin "2") (pinfunction "L2_2") (pintype "passive"))
      (node (ref "L1") (pin "2") (pinfunction "P2_2") (pintype "bidirectional"))
    )
    (net (code "38") (name "Net-(IC6-PROG1)") (class "Default")
      (node (ref "IC6") (pin "13") (pinfunction "PROG1_13") (pintype "bidirectional"))
      (node (ref "R10") (pin "1") (pinfunction "1_1") (pintype "passive"))
    )
    (net (code "39") (name "Net-(IC6-PROG3)") (class "Default")
      (node (ref "IC6") (pin "12") (pinfunction "PROG3_12") (pintype "bidirectional"))
      (node (ref "R9") (pin "1") (pinfunction "1_1") (pintype "passive"))
    )
    (net (code "40") (name "Net-(IC6-THERM)") (class "Default")
      (node (ref "IC6") (pin "5") (pinfunction "THERM_5") (pintype "bidirectional"))
      (node (ref "R11") (pin "1") (pinfunction "1_1") (pintype "passive"))
    )
    (net (code "41") (name "Net-(LED2-BLUE_A)") (class "Default")
      (node (ref "LED2") (pin "3") (pinfunction "BLUE_A_3") (pintype "bidirectional"))
      (node (ref "R19") (pin "1") (pinfunction "1_1") (pintype "passive"))
    )
    (net (code "42") (name "Net-(LED2-GREEN_A)") (class "Default")
      (node (ref "LED2") (pin "1") (pinfunction "GREEN_A_1") (pintype "bidirectional"))
      (node (ref "R18") (pin "1") (pinfunction "1_1") (pintype "passive"))
    )
    (net (code "43") (name "Net-(LED2-RED_A)") (class "Default")
      (node (ref "LED2") (pin "2") (pinfunction "RED_A_2") (pintype "bidirectional"))
      (node (ref "R17") (pin "1") (pinfunction "1_1") (pintype "passive"))
    )
    (net (code "44") (name "Net-(Q3-D)") (class "Default")
      (node (ref "Q3") (pin "3") (pinfunction "D_3") (pintype "passive"))
      (node (ref "R12") (pin "1") (pinfunction "1_1") (pintype "passive"))
    )
    (net (code "45") (name "Net-(Q3-G)") (class "Default")
      (node (ref "Q3") (pin "1") (pinfunction "G_1") (pintype "passive"))
      (node (ref "Q4") (pin "3") (pinfunction "D_3") (pintype "bidirectional"))
      (node (ref "R14") (pin "2") (pinfunction "2_2") (pintype "passive"))
    )
    (net (code "46") (name "Net-(R16-Pad2)") (class "Default")
      (node (ref "R16") (pin "2") (pinfunction "2_2") (pintype "passive"))
      (node (ref "USB1") (pin "2") (pinfunction "2_2") (pintype "input"))
    )
    (net (code "47") (name "Net-(X2-SIGNAL)") (class "Default")
      (node (ref "IC2") (pin "ANT") (pinfunction "ANT_ANT") (pintype "output"))
      (node (ref "X2") (pin "SIG") (pinfunction "SIGNAL_SIG") (pintype "bidirectional"))
    )
    (net (code "48") (name "RESET") (class "Default")
      (node (ref "IC3") (pin "17") (pinfunction "RESET_17") (pintype "bidirectional"))
      (node (ref "R2") (pin "1") (pinfunction "1_1") (pintype "passive"))
      (node (ref "S2") (pin "3") (pinfunction "S_3") (pintype "passive"))
      (node (ref "S2") (pin "4") (pinfunction "S_4") (pintype "passive"))
      (node (ref "U$1") (pin "P$7") (pinfunction "P$7_P$7") (pintype "bidirectional"))
    )
    (net (code "49") (name "RF-GPIO0") (class "Default")
      (node (ref "IC2") (pin "GPIO0") (pinfunction "GPIO0_GPIO0") (pintype "bidirectional"))
      (node (ref "IC3") (pin "58") (pinfunction "P0[20]/DTR1/SCL1_58") (pintype "bidirectional"))
    )
    (net (code "50") (name "RF-NIRQ") (class "Default")
      (node (ref "IC2") (pin "NIRQ") (pinfunction "NIRQ_NIRQ") (pintype "output"))
      (node (ref "IC3") (pin "59") (pinfunction "P0[19]/DSR1/SDA1_59") (pintype "bidirectional"))
    )
    (net (code "51") (name "RF-NSEL") (class "Default")
      (node (ref "IC2") (pin "NSEL") (pinfunction "NSEL_NSEL") (pintype "input"))
      (node (ref "IC3") (pin "63") (pinfunction "P0[16]/RXD1/SSEL0/SSEL_63") (pintype "bidirectional"))
    )
    (net (code "52") (name "RF-SCLK") (class "Default")
      (node (ref "IC2") (pin "SCLK") (pinfunction "SCLK_SCLK") (pintype "input"))
      (node (ref "IC3") (pin "62") (pinfunction "P0[15]/TXD1/SCK0/SCK_62") (pintype "bidirectional"))
    )
    (net (code "53") (name "RF-SDI") (class "Default")
      (node (ref "IC2") (pin "SDI") (pinfunction "SDI_SDI") (pintype "bidirectional"))
      (node (ref "IC3") (pin "60") (pinfunction "P0[18]/DCD1/MOSI0/MOSI_60") (pintype "bidirectional"))
    )
    (net (code "54") (name "RF-SDN") (class "Default")
      (node (ref "IC2") (pin "SDN") (pinfunction "SDN_SDN") (pintype "input"))
      (node (ref "IC3") (pin "65") (pinfunction "P2[8]/TD2/TXD2/ENET_MDC_65") (pintype "bidirectional"))
    )
    (net (code "55") (name "RF-SDO") (class "Default")
      (node (ref "IC2") (pin "SDO") (pinfunction "SDO_SDO") (pintype "output"))
      (node (ref "IC3") (pin "61") (pinfunction "P0[17]/CTS1/MISO0/MISO_61") (pintype "bidirectional"))
    )
    (net (code "56") (name "RX") (class "Default")
      (node (ref "IC3") (pin "99") (pinfunction "P0[3]/RXD0/AD0[6]_99") (pintype "bidirectional"))
      (node (ref "TP2") (pin "TP") (pinfunction "TP_TP") (pintype "input"))
      (node (ref "U$1") (pin "P$5") (pinfunction "P$5_P$5") (pintype "bidirectional"))
    )
    (net (code "57") (name "SCL-EXT") (class "Default")
      (node (ref "IC3") (pin "24") (pinfunction "P0[28]/SCL0/USB_SCL_24") (pintype "bidirectional"))
      (node (ref "U$1") (pin "P$10") (pinfunction "P$10_P$10") (pintype "bidirectional"))
    )
    (net (code "58") (name "SDA-EXT") (class "Default")
      (node (ref "IC3") (pin "25") (pinfunction "P0[27]/SDA0/USB_SDA_25") (pintype "bidirectional"))
      (node (ref "U$1") (pin "P$9") (pinfunction "P$9_P$9") (pintype "bidirectional"))
    )
    (net (code "59") (name "TX") (class "Default")
      (node (ref "IC3") (pin "98") (pinfunction "P0[2]/TXD0/AD0[7]_98") (pintype "bidirectional"))
      (node (ref "TP1") (pin "TP") (pinfunction "TP_TP") (pintype "input"))
      (node (ref "U$1") (pin "P$8") (pinfunction "P$8_P$8") (pintype "bidirectional"))
    )
    (net (code "60") (name "USB-CABLE-D+") (class "Default")
      (node (ref "R15") (pin "2") (pinfunction "2_2") (pintype "passive"))
      (node (ref "R4") (pin "1") (pinfunction "1_1") (pintype "passive"))
      (node (ref "USB1") (pin "3") (pinfunction "3_3") (pintype "input"))
    )
    (net (code "61") (name "USB-D+") (class "Default")
      (node (ref "C22") (pin "1") (pinfunction "1_1") (pintype "passive"))
      (node (ref "IC3") (pin "29") (pinfunction "P0[29]/USB_DPLUS_29") (pintype "bidirectional"))
      (node (ref "R15") (pin "1") (pinfunction "1_1") (pintype "passive"))
    )
    (net (code "62") (name "USB-D-") (class "Default")
      (node (ref "C23") (pin "1") (pinfunction "1_1") (pintype "passive"))
      (node (ref "IC3") (pin "30") (pinfunction "P0[30]/USB_DMINUS_30") (pintype "bidirectional"))
      (node (ref "R16") (pin "1") (pinfunction "1_1") (pintype "passive"))
    )
    (net (code "63") (name "V+") (class "Default")
      (node (ref "C9") (pin "1") (pinfunction "1_1") (pintype "passive"))
      (node (ref "IC6") (pin "14") (pinfunction "VBAT_14") (pintype "bidirectional"))
      (node (ref "IC6") (pin "15") (pinfunction "VBAT2_15") (pintype "bidirectional"))
      (node (ref "IC6") (pin "16") (pinfunction "VBAT_SENSE_16") (pintype "bidirectional"))
      (node (ref "Q3") (pin "2") (pinfunction "S_2") (pintype "passive"))
      (node (ref "R14") (pin "1") (pinfunction "1_1") (pintype "passive"))
      (node (ref "SJ1") (pin "2") (pinfunction "2_2") (pintype "passive"))
    )
    (net (code "64") (name "VCC") (class "Default")
      (node (ref "C10") (pin "1") (pinfunction "1_1") (pintype "passive"))
      (node (ref "C24") (pin "1") (pinfunction "1_1") (pintype "passive"))
      (node (ref "C7") (pin "1") (pinfunction "1_1") (pintype "passive"))
      (node (ref "IC5") (pin "5") (pinfunction "VIN_5") (pintype "input"))
      (node (ref "IC5") (pin "6") (pinfunction "EN_6") (pintype "input"))
      (node (ref "IC5") (pin "8") (pinfunction "VINA_8") (pintype "input"))
      (node (ref "IC6") (pin "1") (pinfunction "OUT_1") (pintype "power_in"))
      (node (ref "IC6") (pin "20") (pinfunction "OUT2_20") (pintype "power_in"))
    )
    (net (code "65") (name "VDD") (class "Default")
      (node (ref "C11") (pin "1") (pinfunction "1_1") (pintype "passive"))
      (node (ref "IC1") (pin "12") (pinfunction "3V3_12") (pintype "bidirectional"))
      (node (ref "Q5") (pin "3") (pinfunction "D_3") (pintype "passive"))
    )
    (net (code "66") (name "VEE") (class "Default")
      (node (ref "C1") (pin "1") (pinfunction "1_1") (pintype "passive"))
      (node (ref "C13") (pin "+") (pinfunction "+_+") (pintype "passive"))
      (node (ref "IC2") (pin "VCC") (pinfunction "VCC_VCC") (pintype "power_in"))
      (node (ref "Q6") (pin "3") (pinfunction "D_3") (pintype "passive"))
    )
    (net (code "67") (name "unconnected-(IC1-AIO0-Pad9)") (class "Default")
      (node (ref "IC1") (pin "9") (pinfunction "AIO0_9") (pintype "bidirectional"))
    )
    (net (code "68") (name "unconnected-(IC1-AIO1-Pad10)") (class "Default")
      (node (ref "IC1") (pin "10") (pinfunction "AIO1_10") (pintype "bidirectional"))
    )
    (net (code "69") (name "unconnected-(IC1-CLK-Pad19)") (class "Default")
      (node (ref "IC1") (pin "19") (pinfunction "CLK_19") (pintype "bidirectional"))
    )
    (net (code "70") (name "unconnected-(IC1-CSB-Pad16)") (class "Default")
      (node (ref "IC1") (pin "16") (pinfunction "CSB_16") (pintype "bidirectional"))
    )
    (net (code "71") (name "unconnected-(IC1-CTS-Pad3)") (class "Default")
      (node (ref "IC1") (pin "3") (pinfunction "CTS_3") (pintype "bidirectional"))
    )
    (net (code "72") (name "unconnected-(IC1-MISO-Pad18)") (class "Default")
      (node (ref "IC1") (pin "18") (pinfunction "MISO_18") (pintype "bidirectional"))
    )
    (net (code "73") (name "unconnected-(IC1-MOSI-Pad17)") (class "Default")
      (node (ref "IC1") (pin "17") (pinfunction "MOSI_17") (pintype "bidirectional"))
    )
    (net (code "74") (name "unconnected-(IC1-NC-Pad14)") (class "Default")
      (node (ref "IC1") (pin "14") (pinfunction "NC_14") (pintype "bidirectional"))
    )
    (net (code "75") (name "unconnected-(IC1-PCM_CLK-Pad5)") (class "Default")
      (node (ref "IC1") (pin "5") (pinfunction "PCM_CLK_5") (pintype "bidirectional"))
    )
    (net (code "76") (name "unconnected-(IC1-PCM_IN-Pad7)") (class "Default")
      (node (ref "IC1") (pin "7") (pinfunction "PCM_IN_7") (pintype "bidirectional"))
    )
    (net (code "77") (name "unconnected-(IC1-PCM_OUT-Pad6)") (class "Default")
      (node (ref "IC1") (pin "6") (pinfunction "PCM_OUT_6") (pintype "bidirectional"))
    )
    (net (code "78") (name "unconnected-(IC1-PCN_SYNC-Pad8)") (class "Default")
      (node (ref "IC1") (pin "8") (pinfunction "PCN_SYNC_8") (pintype "bidirectional"))
    )
    (net (code "79") (name "unconnected-(IC1-PIO0-Pad23)") (class "Default")
      (node (ref "IC1") (pin "23") (pinfunction "PIO0_23") (pintype "bidirectional"))
    )
    (net (code "80") (name "unconnected-(IC1-PIO1-Pad24)") (class "Default")
      (node (ref "IC1") (pin "24") (pinfunction "PIO1_24") (pintype "bidirectional"))
    )
    (net (code "81") (name "unconnected-(IC1-PIO2-Pad25)") (class "Default")
      (node (ref "IC1") (pin "25") (pinfunction "PIO2_25") (pintype "bidirectional"))
    )
    (net (code "82") (name "unconnected-(IC1-PIO3-Pad26)") (class "Default")
      (node (ref "IC1") (pin "26") (pinfunction "PIO3_26") (pintype "bidirectional"))
    )
    (net (code "83") (name "unconnected-(IC1-PIO4-Pad27)") (class "Default")
      (node (ref "IC1") (pin "27") (pinfunction "PIO4_27") (pintype "bidirectional"))
    )
    (net (code "84") (name "unconnected-(IC1-PIO5-Pad28)") (class "Default")
      (node (ref "IC1") (pin "28") (pinfunction "PIO5_28") (pintype "bidirectional"))
    )
    (net (code "85") (name "unconnected-(IC1-PIO6-Pad29)") (class "Default")
      (node (ref "IC1") (pin "29") (pinfunction "PIO6_29") (pintype "bidirectional"))
    )
    (net (code "86") (name "unconnected-(IC1-PIO7-Pad30)") (class "Default")
      (node (ref "IC1") (pin "30") (pinfunction "PIO7_30") (pintype "bidirectional"))
    )
    (net (code "87") (name "unconnected-(IC1-PIO8-Pad31)") (class "Default")
      (node (ref "IC1") (pin "31") (pinfunction "PIO8_31") (pintype "bidirectional"))
    )
    (net (code "88") (name "unconnected-(IC1-PIO10-Pad33)") (class "Default")
      (node (ref "IC1") (pin "33") (pinfunction "PIO10_33") (pintype "bidirectional"))
    )
    (net (code "89") (name "unconnected-(IC1-RTS-Pad4)") (class "Default")
      (node (ref "IC1") (pin "4") (pinfunction "RTS_4") (pintype "bidirectional"))
    )
    (net (code "90") (name "unconnected-(IC1-VBUSD+-Pad20)") (class "Default")
      (node (ref "IC1") (pin "20") (pinfunction "VBUSD+_20") (pintype "bidirectional"))
    )
    (net (code "91") (name "unconnected-(IC1-VBUSD--Pad15)") (class "Default")
      (node (ref "IC1") (pin "15") (pinfunction "VBUSD-_15") (pintype "bidirectional"))
    )
    (net (code "92") (name "unconnected-(IC2-PadGPIO1)") (class "Default")
      (node (ref "IC2") (pin "GPIO1") (pinfunction "GPIO1_GPIO1") (pintype "bidirectional"))
    )
    (net (code "93") (name "unconnected-(IC2-PadNC)") (class "Default")
      (node (ref "IC2") (pin "NC") (pinfunction "NC_NC") (pintype "no_connect"))
    )
    (net (code "94") (name "unconnected-(IC3-NC-Pad13)") (class "Default")
      (node (ref "IC3") (pin "13") (pinfunction "NC_13") (pintype "bidirectional"))
    )
    (net (code "95") (name "unconnected-(IC3-P0[4]{slash}I2SRX_CLK{slash}RD2{slash}CAP2[0]-Pad81)") (class "Default")
      (node (ref "IC3") (pin "81") (pinfunction "P0[4]/I2SRX_CLK/RD2/CAP2[0]_81") (pintype "bidirectional"))
    )
    (net (code "96") (name "unconnected-(IC3-P0[5]{slash}I2SRX_WS{slash}TD2{slash}CAP2[1]-Pad80)") (class "Default")
      (node (ref "IC3") (pin "80") (pinfunction "P0[5]/I2SRX_WS/TD2/CAP2[1]_80") (pintype "bidirectional"))
    )
    (net (code "97") (name "unconnected-(IC3-P0[6]{slash}I2SRX_SDA{slash}SSEL1{slash}MAT2[0]-Pad79)") (class "Default")
      (node (ref "IC3") (pin "79") (pinfunction "P0[6]/I2SRX_SDA/SSEL1/MAT2[0]_79") (pintype "bidirectional"))
    )
    (net (code "98") (name "unconnected-(IC3-P0[7]{slash}I2STX_CLK{slash}SCK1{slash}MAT2[1]-Pad78)") (class "Default")
      (node (ref "IC3") (pin "78") (pinfunction "P0[7]/I2STX_CLK/SCK1/MAT2[1]_78") (pintype "bidirectional"))
    )
    (net (code "99") (name "unconnected-(IC3-P0[10]{slash}TXD2{slash}SDA2{slash}MAT3[0]-Pad48)") (class "Default")
      (node (ref "IC3") (pin "48") (pinfunction "P0[10]/TXD2/SDA2/MAT3[0]_48") (pintype "bidirectional"))
    )
    (net (code "100") (name "unconnected-(IC3-P0[11]{slash}RXD2{slash}SCL2{slash}MAT3[1]-Pad49)") (class "Default")
      (node (ref "IC3") (pin "49") (pinfunction "P0[11]/RXD2/SCL2/MAT3[1]_49") (pintype "bidirectional"))
    )
    (net (code "101") (name "unconnected-(IC3-P1[0]{slash}ENET_TXD0-Pad95)") (class "Default")
      (node (ref "IC3") (pin "95") (pinfunction "P1[0]/ENET_TXD0_95") (pintype "bidirectional"))
    )
    (net (code "102") (name "unconnected-(IC3-P1[1]{slash}ENET_TXD1-Pad94)") (class "Default")
      (node (ref "IC3") (pin "94") (pinfunction "P1[1]/ENET_TXD1_94") (pintype "bidirectional"))
    )
    (net (code "103") (name "unconnected-(IC3-P1[4]{slash}ENET_TX_EN-Pad93)") (class "Default")
      (node (ref "IC3") (pin "93") (pinfunction "P1[4]/ENET_TX_EN_93") (pintype "bidirectional"))
    )
    (net (code "104") (name "unconnected-(IC3-P1[8]{slash}ENET_CRS-Pad92)") (class "Default")
      (node (ref "IC3") (pin "92") (pinfunction "P1[8]/ENET_CRS_92") (pintype "bidirectional"))
    )
    (net (code "105") (name "unconnected-(IC3-P1[9]{slash}ENET_RXD0-Pad91)") (class "Default")
      (node (ref "IC3") (pin "91") (pinfunction "P1[9]/ENET_RXD0_91") (pintype "bidirectional"))
    )
    (net (code "106") (name "unconnected-(IC3-P1[10]{slash}ENET_RXD1-Pad90)") (class "Default")
      (node (ref "IC3") (pin "90") (pinfunction "P1[10]/ENET_RXD1_90") (pintype "bidirectional"))
    )
    (net (code "107") (name "unconnected-(IC3-P1[14]{slash}ENET_RX_ER-Pad89)") (class "Default")
      (node (ref "IC3") (pin "89") (pinfunction "P1[14]/ENET_RX_ER_89") (pintype "bidirectional"))
    )
    (net (code "108") (name "unconnected-(IC3-P1[15]{slash}ENET_REF_CLK-Pad88)") (class "Default")
      (node (ref "IC3") (pin "88") (pinfunction "P1[15]/ENET_REF_CLK_88") (pintype "bidirectional"))
    )
    (net (code "109") (name "unconnected-(IC3-P1[16]{slash}ENET_MDC-Pad87)") (class "Default")
      (node (ref "IC3") (pin "87") (pinfunction "P1[16]/ENET_MDC_87") (pintype "bidirectional"))
    )
    (net (code "110") (name "unconnected-(IC3-P1[19]{slash}MCOA0{slash}USB_PPWR{slash}CAP1[1]-Pad33)") (class "Default")
      (node (ref "IC3") (pin "33") (pinfunction "P1[19]/MCOA0/USB_PPWR/CAP1[1]_33") (pintype "bidirectional"))
    )
    (net (code "111") (name "unconnected-(IC3-P1[22]{slash}MCOB0{slash}USB_PWRD{slash}MAT1[0]-Pad36)") (class "Default")
      (node (ref "IC3") (pin "36") (pinfunction "P1[22]/MCOB0/USB_PWRD/MAT1[0]_36") (pintype "bidirectional"))
    )
    (net (code "112") (name "unconnected-(IC3-P1[23]{slash}MCI1{slash}PWM1[4]{slash}MISO0-Pad37)") (class "Default")
      (node (ref "IC3") (pin "37") (pinfunction "P1[23]/MCI1/PWM1[4]/MISO0_37") (pintype "bidirectional"))
    )
    (net (code "113") (name "unconnected-(IC3-P1[24]{slash}MCI2{slash}PWM1[5]{slash}MOSI0-Pad38)") (class "Default")
      (node (ref "IC3") (pin "38") (pinfunction "P1[24]/MCI2/PWM1[5]/MOSI0_38") (pintype "bidirectional"))
    )
    (net (code "114") (name "unconnected-(IC3-P1[25]{slash}MCOA1{slash}MAT1[1]-Pad39)") (class "Default")
      (node (ref "IC3") (pin "39") (pinfunction "P1[25]/MCOA1/MAT1[1]_39") (pintype "bidirectional"))
    )
    (net (code "115") (name "unconnected-(IC3-P1[26]{slash}MCOB1{slash}PWM1[6]{slash}CAP0[0]-Pad40)") (class "Default")
      (node (ref "IC3") (pin "40") (pinfunction "P1[26]/MCOB1/PWM1[6]/CAP0[0]_40") (pintype "bidirectional"))
    )
    (net (code "116") (name "unconnected-(IC3-P1[27]{slash}CLKOUT{slash}USB_OVRCR{slash}CAP0[1]-Pad43)") (class "Default")
      (node (ref "IC3") (pin "43") (pinfunction "P1[27]/CLKOUT/USB_OVRCR/CAP0[1]_43") (pintype "bidirectional"))
    )
    (net (code "117") (name "unconnected-(IC3-P1[28]{slash}MCOA2{slash}PCAP1[0]{slash}MAT0[0]-Pad44)") (class "Default")
      (node (ref "IC3") (pin "44") (pinfunction "P1[28]/MCOA2/PCAP1[0]/MAT0[0]_44") (pintype "bidirectional"))
    )
    (net (code "118") (name "unconnected-(IC3-P1[29]{slash}MCOB2{slash}PCAP1[1]{slash}MAT0[1]-Pad45)") (class "Default")
      (node (ref "IC3") (pin "45") (pinfunction "P1[29]/MCOB2/PCAP1[1]/MAT0[1]_45") (pintype "bidirectional"))
    )
    (net (code "119") (name "unconnected-(IC3-P1[30]{slash}VBUS{slash}AD0[4]-Pad21)") (class "Default")
      (node (ref "IC3") (pin "21") (pinfunction "P1[30]/VBUS/AD0[4]_21") (pintype "bidirectional"))
    )
    (net (code "120") (name "unconnected-(IC3-P1[31]{slash}SCK1{slash}AD0[5]-Pad20)") (class "Default")
      (node (ref "IC3") (pin "20") (pinfunction "P1[31]/SCK1/AD0[5]_20") (pintype "bidirectional"))
    )
    (net (code "121") (name "unconnected-(IC3-P2[0]{slash}PWM1[1]{slash}TXD1-Pad75)") (class "Default")
      (node (ref "IC3") (pin "75") (pinfunction "P2[0]/PWM1[1]/TXD1_75") (pintype "bidirectional"))
    )
    (net (code "122") (name "unconnected-(IC3-P2[1]{slash}PWM1[2]{slash}RXD1-Pad74)") (class "Default")
      (node (ref "IC3") (pin "74") (pinfunction "P2[1]/PWM1[2]/RXD1_74") (pintype "bidirectional"))
    )
    (net (code "123") (name "unconnected-(IC3-P2[2]{slash}PWM1[3]{slash}CTS1{slash}TRACEDATA[3]-Pad73)") (class "Default")
      (node (ref "IC3") (pin "73") (pinfunction "P2[2]/PWM1[3]/CTS1/TRACEDATA[3]_73") (pintype "bidirectional"))
    )
    (net (code "124") (name "unconnected-(IC3-P2[5]{slash}PWM1[6]{slash}DTR1{slash}TRACEDATA[0]-Pad68)") (class "Default")
      (node (ref "IC3") (pin "68") (pinfunction "P2[5]/PWM1[6]/DTR1/TRACEDATA[0]_68") (pintype "bidirectional"))
    )
    (net (code "125") (name "unconnected-(IC3-P2[6]{slash}PCAP1[0]{slash}RI1{slash}TRACECLK-Pad67)") (class "Default")
      (node (ref "IC3") (pin "67") (pinfunction "P2[6]/PCAP1[0]/RI1/TRACECLK_67") (pintype "bidirectional"))
    )
    (net (code "126") (name "unconnected-(IC3-P2[7]{slash}RD2{slash}RTS1-Pad66)") (class "Default")
      (node (ref "IC3") (pin "66") (pinfunction "P2[7]/RD2/RTS1_66") (pintype "bidirectional"))
    )
    (net (code "127") (name "unconnected-(IC3-P2[13]{slash}EINT3{slash}I2STX_SDA-Pad50)") (class "Default")
      (node (ref "IC3") (pin "50") (pinfunction "P2[13]/EINT3/I2STX_SDA_50") (pintype "bidirectional"))
    )
    (net (code "128") (name "unconnected-(IC3-P4[28]{slash}RX_MCLK{slash}MAT2[0]{slash}TXD3-Pad82)") (class "Default")
      (node (ref "IC3") (pin "82") (pinfunction "P4[28]/RX_MCLK/MAT2[0]/TXD3_82") (pintype "bidirectional"))
    )
    (net (code "129") (name "unconnected-(IC3-P4[29]{slash}TX_MCLK{slash}MAT2[1]{slash}RXD3-Pad85)") (class "Default")
      (node (ref "IC3") (pin "85") (pinfunction "P4[29]/TX_MCLK/MAT2[1]/RXD3_85") (pintype "bidirectional"))
    )
    (net (code "130") (name "unconnected-(IC3-RSTOUT-Pad14)") (class "Default")
      (node (ref "IC3") (pin "14") (pinfunction "RSTOUT_14") (pintype "bidirectional"))
    )
    (net (code "131") (name "unconnected-(IC3-RTCK-Pad100)") (class "Default")
      (node (ref "IC3") (pin "100") (pinfunction "RTCK_100") (pintype "bidirectional"))
    )
    (net (code "132") (name "unconnected-(IC6-{slash}PG-Pad6)") (class "Default")
      (node (ref "IC6") (pin "6") (pinfunction "/PG_6") (pintype "open_collector"))
    )
    (net (code "133") (name "unconnected-(USB1-Pad4)") (class "Default")
      (node (ref "USB1") (pin "4") (pinfunction "4_4") (pintype "input"))
    )
    (net (code "134") (name "{slash}BT-ON") (class "Default")
      (node (ref "IC3") (pin "26") (pinfunction "P3[26]/STCLK/MAT0[1]/PWM1[3]_26") (pintype "bidirectional"))
      (node (ref "Q5") (pin "1") (pinfunction "G_1") (pintype "passive"))
    )
    (net (code "135") (name "{slash}RF-ON") (class "Default")
      (node (ref "IC3") (pin "76") (pinfunction "P0[9]/I2STX_SDA/MOSI1/MAT2[3]_76") (pintype "bidirectional"))
      (node (ref "Q6") (pin "1") (pinfunction "G_1") (pintype "passive"))
    )
  )
)
